# g5gate-min132.net
KiCad netlist of a schematic drawn in EAGLE
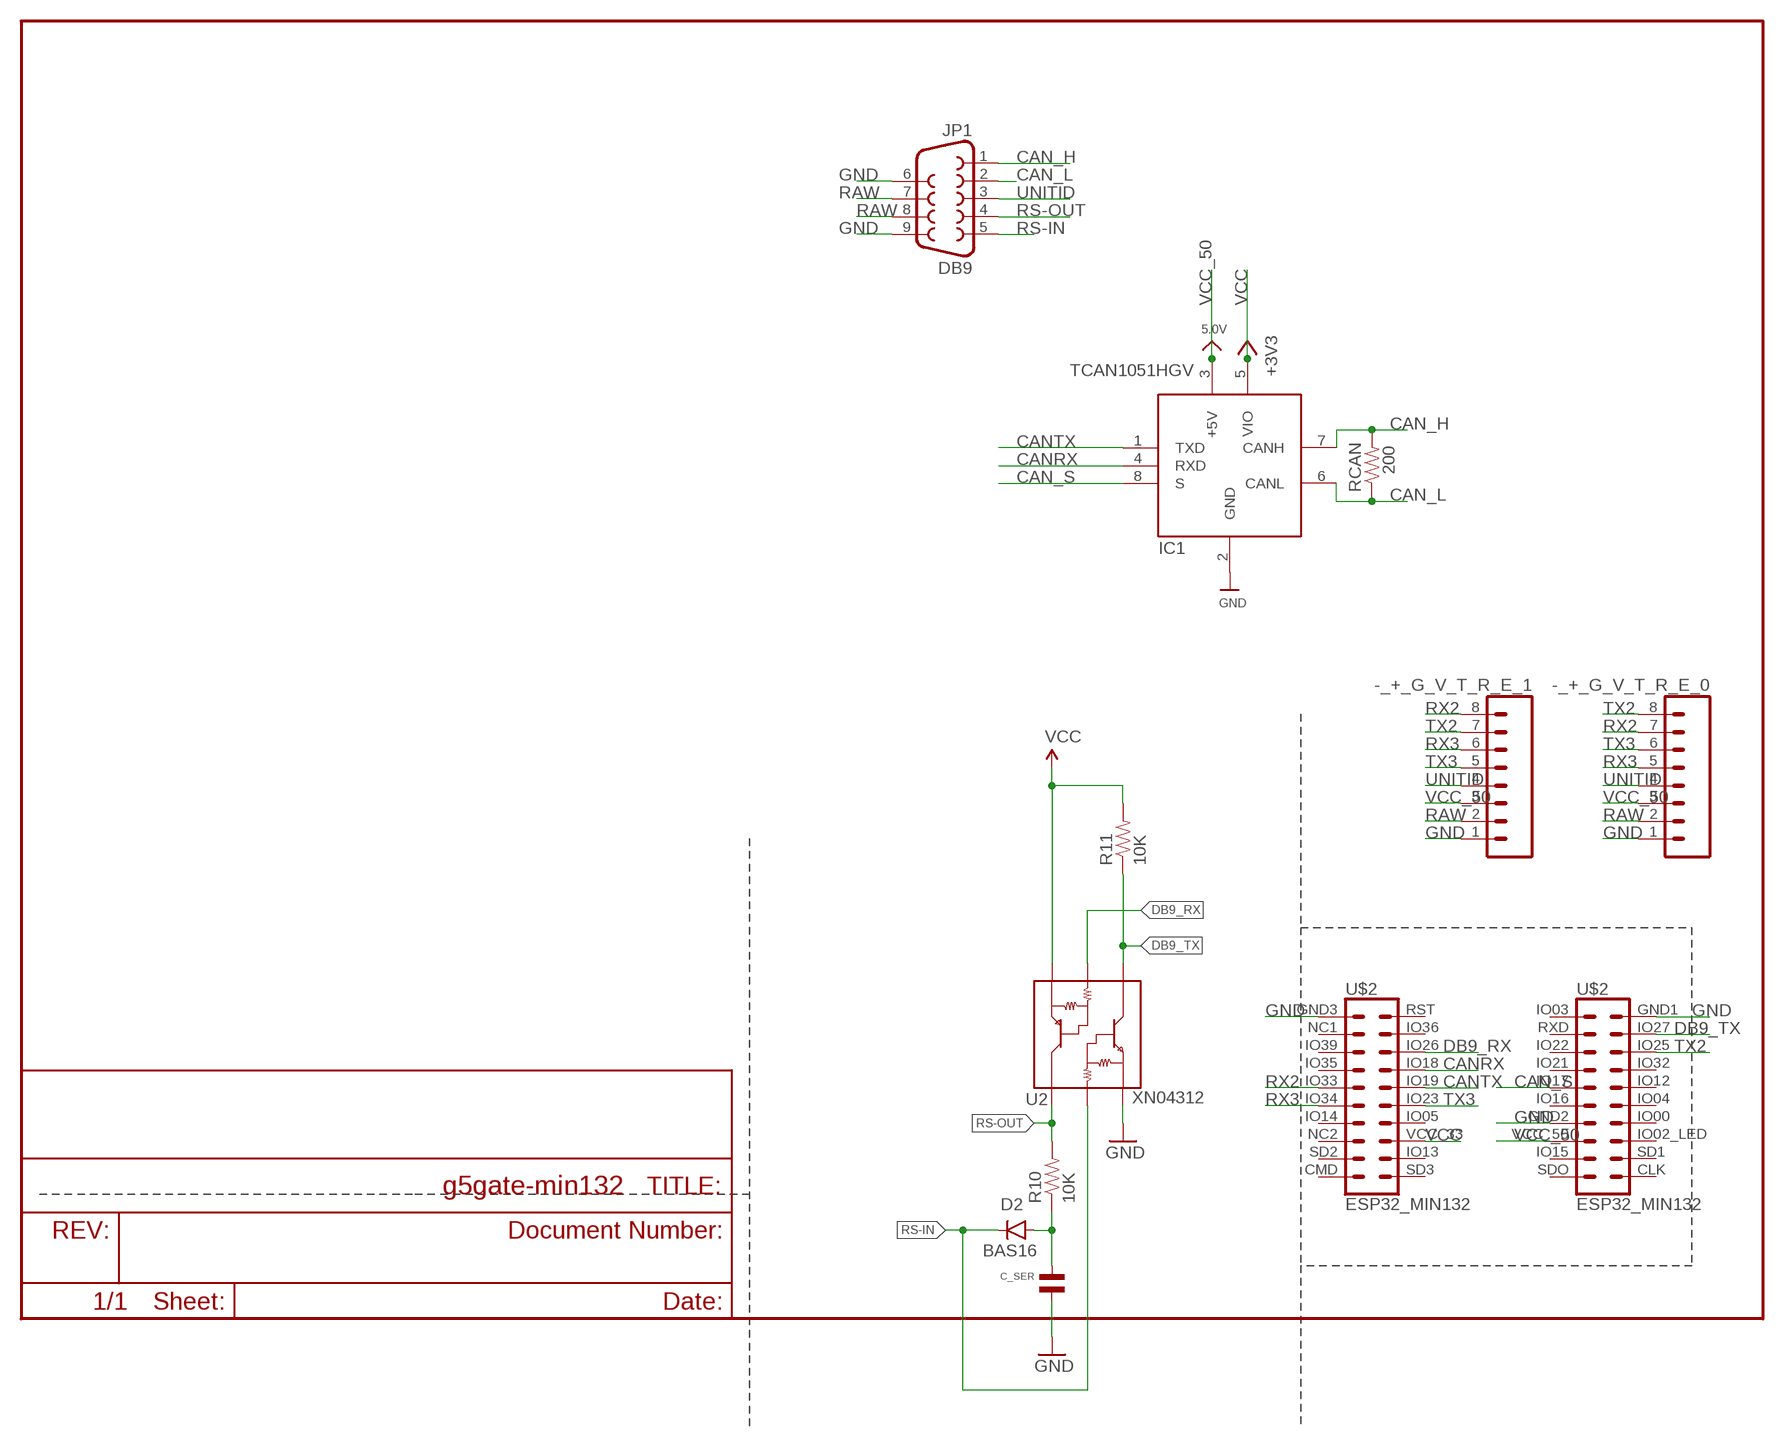
[diagram p0: schematic, sheet 1]

(export (version "E")
  (design (tool "Eeschema 10.0.6"))
  (components
    (comp (ref "-_+_G_V_T_R_E_0")
      (value "MF-CON-2.54mm-01x08")
      (footprint "eagle-import:1X08")
      (libsource (lib "eagle-import") (part "M081X08"))
    )
    (comp (ref "-_+_G_V_T_R_E_1")
      (value "MF-CON-2.54mm-01x08")
      (footprint "eagle-import:1X08")
      (libsource (lib "eagle-import") (part "M081X08"))
    )
    (comp (ref "C_SER")
      (value "CAPACITOR_NP_0603")
      (footprint "eagle-import:C0603")
      (libsource (lib "eagle-import") (part "CAPACITOR_NP_0603"))
    )
    (comp (ref "D2")
      (value "BAS16")
      (footprint "eagle-import:SOD-323")
      (libsource (lib "eagle-import") (part "DIODEBAS16"))
    )
    (comp (ref "IC1")
      (value "TCAN1051HGV")
      (footprint "eagle-import:SOIC8_150MIL")
      (libsource (lib "eagle-import") (part "CAN_TRANSCIEVER_TCAN1051V"))
    )
    (comp (ref "JP1")
      (value "DB9")
      (footprint "eagle-import:DB9")
      (libsource (lib "eagle-import") (part "DB9FEMALE"))
    )
    (comp (ref "R10")
      (value "10K")
      (footprint "eagle-import:0603-RES")
      (libsource (lib "eagle-import") (part "10KOHM1/10W1%(0603)0603"))
    )
    (comp (ref "R11")
      (value "10K")
      (footprint "eagle-import:0603-RES")
      (libsource (lib "eagle-import") (part "10KOHM1/10W1%(0603)0603"))
    )
    (comp (ref "RCAN")
      (value "200")
      (footprint "eagle-import:0603-RES")
      (libsource (lib "eagle-import") (part "10KOHM1/10W1%(0603)0603"))
    )
    (comp (ref "U$2")
      (value "ESP32_MIN132")
      (footprint "eagle-import:ESP32_MIN132")
      (libsource (lib "eagle-import") (part "ESP32_MIN132"))
    )
    (comp (ref "U2")
      (value "XN04312")
      (footprint "eagle-import:SOT23-6")
      (libsource (lib "eagle-import") (part "XN04312SOT"))
    )
  )
  (nets
    (net (code "1") (name "+3V3") (class "Default")
      (node (ref "IC1") (pin "5") (pinfunction "VIO_5") (pintype "power_in"))
      (node (ref "R11") (pin "2") (pinfunction "2_2") (pintype "passive"))
      (node (ref "U$2") (pin "VCC_33") (pinfunction "16_VCC_33") (pintype "passive"))
      (node (ref "U2") (pin "3") (pinfunction "E2_3") (pintype "bidirectional"))
    )
    (net (code "2") (name "/CANRX") (class "Default")
      (node (ref "IC1") (pin "4") (pinfunction "RXD_4") (pintype "output"))
      (node (ref "U$2") (pin "IO18") (pinfunction "8_IO18") (pintype "passive"))
    )
    (net (code "3") (name "/CANTX") (class "Default")
      (node (ref "IC1") (pin "1") (pinfunction "TXD_1") (pintype "input"))
      (node (ref "U$2") (pin "IO19") (pinfunction "10_IO19") (pintype "passive"))
    )
    (net (code "4") (name "/CAN_H") (class "Default")
      (node (ref "IC1") (pin "7") (pinfunction "CANH_7") (pintype "bidirectional"))
      (node (ref "JP1") (pin "1") (pinfunction "1_1") (pintype "passive"))
      (node (ref "RCAN") (pin "2") (pinfunction "2_2") (pintype "passive"))
    )
    (net (code "5") (name "/CAN_L") (class "Default")
      (node (ref "IC1") (pin "6") (pinfunction "CANL_6") (pintype "bidirectional"))
      (node (ref "JP1") (pin "2") (pinfunction "2_2") (pintype "passive"))
      (node (ref "RCAN") (pin "1") (pinfunction "1_1") (pintype "passive"))
    )
    (net (code "6") (name "/CAN_S") (class "Default")
      (node (ref "IC1") (pin "8") (pinfunction "S_8") (pintype "input"))
      (node (ref "U$2") (pin "IO17") (pinfunction "29_IO17") (pintype "passive"))
    )
    (net (code "7") (name "/RAW") (class "Default")
      (node (ref "-_+_G_V_T_R_E_0") (pin "2") (pinfunction "2_2") (pintype "passive"))
      (node (ref "-_+_G_V_T_R_E_1") (pin "2") (pinfunction "2_2") (pintype "passive"))
      (node (ref "JP1") (pin "7") (pinfunction "7_7") (pintype "passive"))
      (node (ref "JP1") (pin "8") (pinfunction "8_8") (pintype "passive"))
    )
    (net (code "8") (name "/RX2") (class "Default")
      (node (ref "-_+_G_V_T_R_E_0") (pin "7") (pinfunction "7_7") (pintype "passive"))
      (node (ref "-_+_G_V_T_R_E_1") (pin "8") (pinfunction "8_8") (pintype "passive"))
      (node (ref "U$2") (pin "IO33") (pinfunction "9_IO33") (pintype "passive"))
    )
    (net (code "9") (name "/RX3") (class "Default")
      (node (ref "-_+_G_V_T_R_E_0") (pin "5") (pinfunction "5_5") (pintype "passive"))
      (node (ref "-_+_G_V_T_R_E_1") (pin "6") (pinfunction "6_6") (pintype "passive"))
      (node (ref "U$2") (pin "IO34") (pinfunction "11_IO34") (pintype "passive"))
    )
    (net (code "10") (name "/TX2") (class "Default")
      (node (ref "-_+_G_V_T_R_E_0") (pin "8") (pinfunction "8_8") (pintype "passive"))
      (node (ref "-_+_G_V_T_R_E_1") (pin "7") (pinfunction "7_7") (pintype "passive"))
      (node (ref "U$2") (pin "IO25") (pinfunction "26_IO25") (pintype "passive"))
    )
    (net (code "11") (name "/TX3") (class "Default")
      (node (ref "-_+_G_V_T_R_E_0") (pin "6") (pinfunction "6_6") (pintype "passive"))
      (node (ref "-_+_G_V_T_R_E_1") (pin "5") (pinfunction "5_5") (pintype "passive"))
      (node (ref "U$2") (pin "IO23") (pinfunction "12_IO23") (pintype "passive"))
    )
    (net (code "12") (name "/UNITID") (class "Default")
      (node (ref "-_+_G_V_T_R_E_0") (pin "4") (pinfunction "4_4") (pintype "passive"))
      (node (ref "-_+_G_V_T_R_E_1") (pin "4") (pinfunction "4_4") (pintype "passive"))
      (node (ref "JP1") (pin "3") (pinfunction "3_3") (pintype "passive"))
    )
    (net (code "13") (name "5.0V") (class "Default")
      (node (ref "-_+_G_V_T_R_E_0") (pin "3") (pinfunction "3_3") (pintype "passive"))
      (node (ref "-_+_G_V_T_R_E_1") (pin "3") (pinfunction "3_3") (pintype "passive"))
      (node (ref "IC1") (pin "3") (pinfunction "+5V_3") (pintype "power_in"))
      (node (ref "U$2") (pin "VCC_50") (pinfunction "35_VCC_50") (pintype "passive"))
    )
    (net (code "14") (name "DB9_RX") (class "Default")
      (node (ref "U$2") (pin "IO26") (pinfunction "6_IO26") (pintype "passive"))
      (node (ref "U2") (pin "2") (pinfunction "B2_2") (pintype "bidirectional"))
    )
    (net (code "15") (name "DB9_TX") (class "Default")
      (node (ref "R11") (pin "1") (pinfunction "1_1") (pintype "passive"))
      (node (ref "U$2") (pin "IO27") (pinfunction "24_IO27") (pintype "passive"))
      (node (ref "U2") (pin "1") (pinfunction "C1_1") (pintype "bidirectional"))
    )
    (net (code "16") (name "GND") (class "Default")
      (node (ref "-_+_G_V_T_R_E_0") (pin "1") (pinfunction "1_1") (pintype "passive"))
      (node (ref "-_+_G_V_T_R_E_1") (pin "1") (pinfunction "1_1") (pintype "passive"))
      (node (ref "C_SER") (pin "P$2") (pinfunction "P$2_P$2") (pintype "passive"))
      (node (ref "IC1") (pin "2") (pinfunction "GND_2") (pintype "power_in"))
      (node (ref "JP1") (pin "6") (pinfunction "6_6") (pintype "passive"))
      (node (ref "JP1") (pin "9") (pinfunction "9_9") (pintype "passive"))
      (node (ref "U$2") (pin "GND1") (pinfunction "22_GND1") (pintype "passive"))
      (node (ref "U$2") (pin "GND2") (pinfunction "33_GND2") (pintype "passive"))
      (node (ref "U$2") (pin "GND3") (pinfunction "1_GND3") (pintype "passive"))
      (node (ref "U2") (pin "6") (pinfunction "E1_6") (pintype "bidirectional"))
    )
    (net (code "17") (name "Net-(C_SER-PadP$1)") (class "Default")
      (node (ref "C_SER") (pin "P$1") (pinfunction "P$1_P$1") (pintype "passive"))
      (node (ref "D2") (pin "A") (pinfunction "A_A") (pintype "passive"))
      (node (ref "R10") (pin "1") (pinfunction "1_1") (pintype "passive"))
    )
    (net (code "18") (name "RS-IN") (class "Default")
      (node (ref "D2") (pin "C") (pinfunction "C_C") (pintype "passive"))
      (node (ref "JP1") (pin "5") (pinfunction "5_5") (pintype "passive"))
      (node (ref "U2") (pin "5") (pinfunction "B1_5") (pintype "bidirectional"))
    )
    (net (code "19") (name "RS-OUT") (class "Default")
      (node (ref "JP1") (pin "4") (pinfunction "4_4") (pintype "passive"))
      (node (ref "R10") (pin "2") (pinfunction "2_2") (pintype "passive"))
      (node (ref "U2") (pin "4") (pinfunction "C2_4") (pintype "bidirectional"))
    )
    (net (code "20") (name "unconnected-(U$2-2-PadRST)") (class "Default")
      (node (ref "U$2") (pin "RST") (pinfunction "2_RST") (pintype "passive"))
    )
    (net (code "21") (name "unconnected-(U$2-3-PadNC1)") (class "Default")
      (node (ref "U$2") (pin "NC1") (pinfunction "3_NC1") (pintype "passive"))
    )
    (net (code "22") (name "unconnected-(U$2-4-PadIO36)") (class "Default")
      (node (ref "U$2") (pin "IO36") (pinfunction "4_IO36") (pintype "passive"))
    )
    (net (code "23") (name "unconnected-(U$2-5-PadIO39)") (class "Default")
      (node (ref "U$2") (pin "IO39") (pinfunction "5_IO39") (pintype "passive"))
    )
    (net (code "24") (name "unconnected-(U$2-7-PadIO35)") (class "Default")
      (node (ref "U$2") (pin "IO35") (pinfunction "7_IO35") (pintype "passive"))
    )
    (net (code "25") (name "unconnected-(U$2-13-PadIO14)") (class "Default")
      (node (ref "U$2") (pin "IO14") (pinfunction "13_IO14") (pintype "passive"))
    )
    (net (code "26") (name "unconnected-(U$2-14-PadIO05)") (class "Default")
      (node (ref "U$2") (pin "IO05") (pinfunction "14_IO05") (pintype "passive"))
    )
    (net (code "27") (name "unconnected-(U$2-15-PadNC2)") (class "Default")
      (node (ref "U$2") (pin "NC2") (pinfunction "15_NC2") (pintype "passive"))
    )
    (net (code "28") (name "unconnected-(U$2-17-PadSD2)") (class "Default")
      (node (ref "U$2") (pin "SD2") (pinfunction "17_SD2") (pintype "passive"))
    )
    (net (code "29") (name "unconnected-(U$2-18-PadIO13)") (class "Default")
      (node (ref "U$2") (pin "IO13") (pinfunction "18_IO13") (pintype "passive"))
    )
    (net (code "30") (name "unconnected-(U$2-19-PadCMD)") (class "Default")
      (node (ref "U$2") (pin "CMD") (pinfunction "19_CMD") (pintype "passive"))
    )
    (net (code "31") (name "unconnected-(U$2-20-PadSD3)") (class "Default")
      (node (ref "U$2") (pin "SD3") (pinfunction "20_SD3") (pintype "passive"))
    )
    (net (code "32") (name "unconnected-(U$2-21-PadIO03)") (class "Default")
      (node (ref "U$2") (pin "IO03") (pinfunction "21_IO03") (pintype "passive"))
    )
    (net (code "33") (name "unconnected-(U$2-23-PadRXD)") (class "Default")
      (node (ref "U$2") (pin "RXD") (pinfunction "23_RXD") (pintype "passive"))
    )
    (net (code "34") (name "unconnected-(U$2-25-PadIO22)") (class "Default")
      (node (ref "U$2") (pin "IO22") (pinfunction "25_IO22") (pintype "passive"))
    )
    (net (code "35") (name "unconnected-(U$2-27-PadIO21)") (class "Default")
      (node (ref "U$2") (pin "IO21") (pinfunction "27_IO21") (pintype "passive"))
    )
    (net (code "36") (name "unconnected-(U$2-28-PadIO32)") (class "Default")
      (node (ref "U$2") (pin "IO32") (pinfunction "28_IO32") (pintype "passive"))
    )
    (net (code "37") (name "unconnected-(U$2-30-PadIO12)") (class "Default")
      (node (ref "U$2") (pin "IO12") (pinfunction "30_IO12") (pintype "passive"))
    )
    (net (code "38") (name "unconnected-(U$2-31-PadIO16)") (class "Default")
      (node (ref "U$2") (pin "IO16") (pinfunction "31_IO16") (pintype "passive"))
    )
    (net (code "39") (name "unconnected-(U$2-32-PadIO04)") (class "Default")
      (node (ref "U$2") (pin "IO04") (pinfunction "32_IO04") (pintype "passive"))
    )
    (net (code "40") (name "unconnected-(U$2-34-PadIO00)") (class "Default")
      (node (ref "U$2") (pin "IO00") (pinfunction "34_IO00") (pintype "passive"))
    )
    (net (code "41") (name "unconnected-(U$2-36-PadIO02_LED)") (class "Default")
      (node (ref "U$2") (pin "IO02_LED") (pinfunction "36_IO02_LED") (pintype "passive"))
    )
    (net (code "42") (name "unconnected-(U$2-37-PadIO15)") (class "Default")
      (node (ref "U$2") (pin "IO15") (pinfunction "37_IO15") (pintype "passive"))
    )
    (net (code "43") (name "unconnected-(U$2-38-PadSD1)") (class "Default")
      (node (ref "U$2") (pin "SD1") (pinfunction "38_SD1") (pintype "passive"))
    )
    (net (code "44") (name "unconnected-(U$2-39-PadSDO)") (class "Default")
      (node (ref "U$2") (pin "SDO") (pinfunction "39_SDO") (pintype "passive"))
    )
    (net (code "45") (name "unconnected-(U$2-40-PadCLK)") (class "Default")
      (node (ref "U$2") (pin "CLK") (pinfunction "40_CLK") (pintype "passive"))
    )
  )
)
